# STM32_BalanceCar.net
KiCad netlist of a schematic drawn in Altium Designer
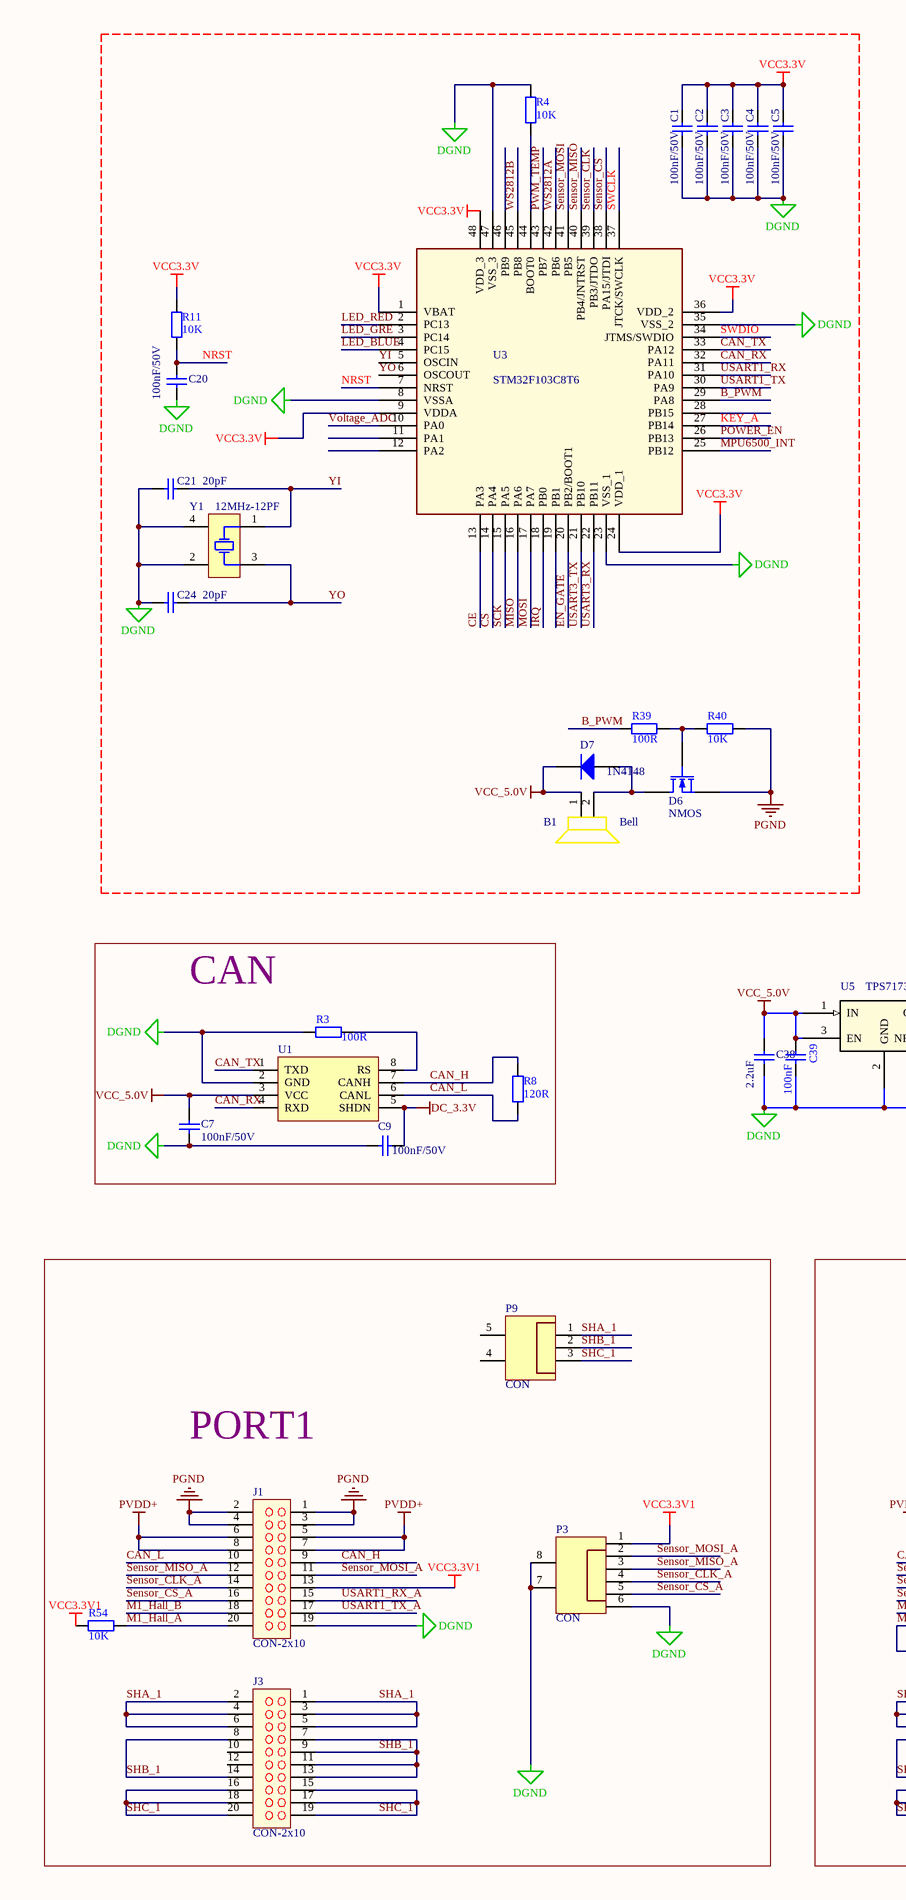
[diagram p0: STM32_BalanceCar.SchDoc, left]
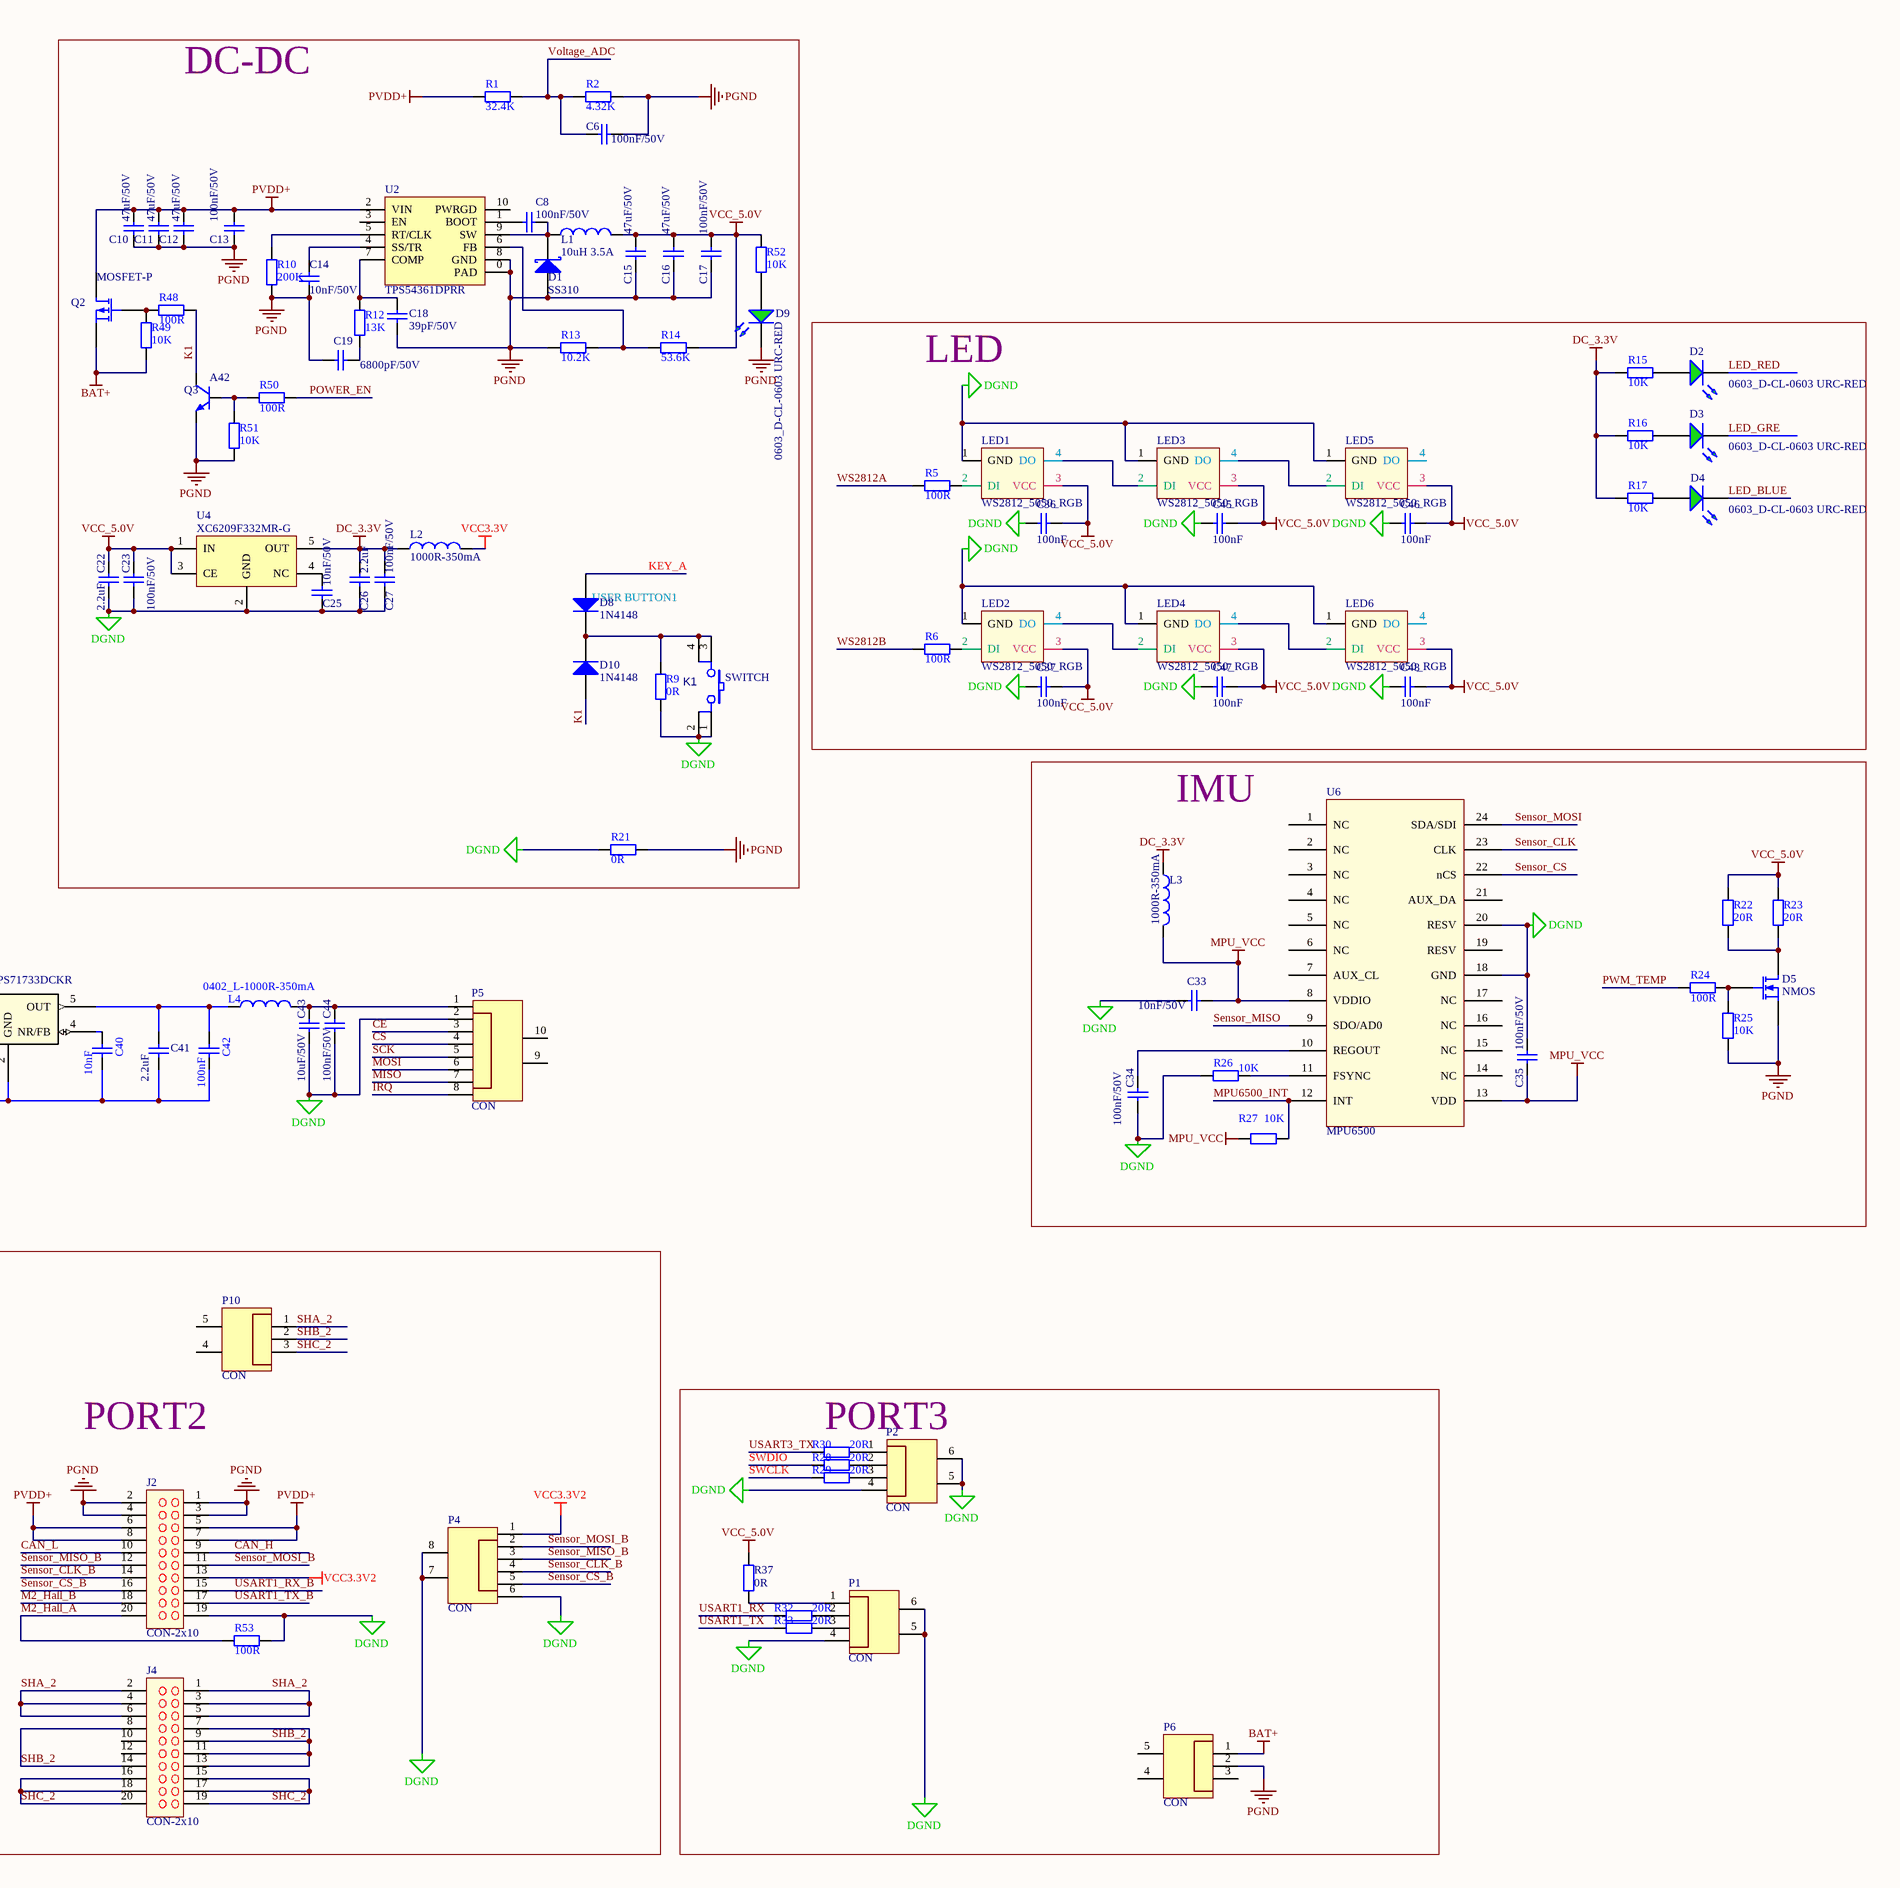
[diagram p1: STM32_BalanceCar.SchDoc, right]

(export (version "E")
  (design (tool "Eeschema 10.0.6"))
  (components
    (comp (ref "B1") (value "Bell") (footprint "Bell") (libsource (lib "Bell") (part "Bell")))
    (comp (ref "C1")
      (value "100nF/50V")
      (footprint "0402_C")
      (description "Capacitor")
      (fields (field (name "PUBLISHER") "Altium Limited"))
      (libsource (lib "") (part "Cap_1"))
    )
    (comp (ref "C2")
      (value "100nF/50V")
      (footprint "0402_C")
      (description "Capacitor")
      (fields (field (name "PUBLISHER") "Altium Limited"))
      (libsource (lib "") (part "Cap_1"))
    )
    (comp (ref "C3")
      (value "100nF/50V")
      (footprint "0402_C")
      (description "Capacitor")
      (fields (field (name "PUBLISHER") "Altium Limited"))
      (libsource (lib "") (part "Cap_1"))
    )
    (comp (ref "C4")
      (value "100nF/50V")
      (footprint "0402_C")
      (description "Capacitor")
      (fields (field (name "PUBLISHER") "Altium Limited"))
      (libsource (lib "") (part "Cap_1"))
    )
    (comp (ref "C5")
      (value "100nF/50V")
      (footprint "0402_C")
      (description "Capacitor")
      (fields (field (name "PUBLISHER") "Altium Limited"))
      (libsource (lib "") (part "Cap_1"))
    )
    (comp (ref "C6")
      (value "100nF/50V")
      (footprint "0402_C")
      (description "Capacitor")
      (fields (field (name "PUBLISHER") "Altium Limited"))
      (libsource (lib "") (part "Cap_1"))
    )
    (comp (ref "C7")
      (value "100nF/50V")
      (footprint "0402_C")
      (description "Capacitor")
      (fields (field (name "PUBLISHER") "Altium Limited"))
      (libsource (lib "Miscellaneous Devices") (part "Cap"))
    )
    (comp (ref "C8")
      (value "100nF/50V")
      (footprint "0402_C")
      (description "Capacitor")
      (fields (field (name "PUBLISHER") "Altium Limited"))
      (libsource (lib "") (part "Cap_1"))
    )
    (comp (ref "C9")
      (value "100nF/50V")
      (footprint "0402_C")
      (description "Capacitor")
      (fields (field (name "PUBLISHER") "Altium Limited"))
      (libsource (lib "") (part "Cap_1"))
    )
    (comp (ref "C10")
      (value "47uF/50V")
      (footprint "1210_C")
      (description "Capacitor")
      (fields (field (name "PUBLISHER") "Altium Limited"))
      (libsource (lib "Miscellaneous Devices") (part "Cap"))
    )
    (comp (ref "C11")
      (value "47uF/50V")
      (footprint "1210_C")
      (description "Capacitor")
      (fields (field (name "PUBLISHER") "Altium Limited"))
      (libsource (lib "Miscellaneous Devices") (part "Cap"))
    )
    (comp (ref "C12")
      (value "47uF/50V")
      (footprint "1210_C")
      (description "Capacitor")
      (fields (field (name "PUBLISHER") "Altium Limited"))
      (libsource (lib "Miscellaneous Devices") (part "Cap"))
    )
    (comp (ref "C13")
      (value "100nF/50V")
      (footprint "0402_C")
      (description "Capacitor")
      (fields (field (name "PUBLISHER") "Altium Limited"))
      (libsource (lib "") (part "Cap_1"))
    )
    (comp (ref "C14")
      (value "10nF/50V")
      (footprint "0402_C")
      (description "Capacitor")
      (fields (field (name "PUBLISHER") "Altium Limited"))
      (libsource (lib "Miscellaneous Devices") (part "Cap"))
    )
    (comp (ref "C15")
      (value "47uF/50V")
      (footprint "1206_C")
      (description "Capacitor")
      (fields (field (name "PUBLISHER") "Altium Limited"))
      (libsource (lib "Miscellaneous Devices") (part "Cap"))
    )
    (comp (ref "C16")
      (value "47uF/50V")
      (footprint "1206_C")
      (description "Capacitor")
      (fields (field (name "PUBLISHER") "Altium Limited"))
      (libsource (lib "Miscellaneous Devices") (part "Cap"))
    )
    (comp (ref "C17")
      (value "100nF/50V")
      (footprint "0402_C")
      (description "Capacitor")
      (fields (field (name "PUBLISHER") "Altium Limited"))
      (libsource (lib "") (part "Cap_1"))
    )
    (comp (ref "C18")
      (value "39pF/50V")
      (footprint "0402_C")
      (description "Capacitor")
      (fields (field (name "PUBLISHER") "Altium Limited"))
      (libsource (lib "Miscellaneous Devices") (part "Cap"))
    )
    (comp (ref "C19")
      (value "6800pF/50V")
      (footprint "0402_C")
      (description "Capacitor")
      (fields (field (name "PUBLISHER") "Altium Limited"))
      (libsource (lib "") (part "Cap_1"))
    )
    (comp (ref "C20")
      (value "100nF/50V")
      (footprint "0402_C")
      (description "Capacitor")
      (fields (field (name "PUBLISHER") "Altium Limited"))
      (libsource (lib "") (part "Cap_1"))
    )
    (comp (ref "C21")
      (value "20pF")
      (footprint "0402_C")
      (description "Capacitor")
      (fields (field (name "PUBLISHER") "Altium Limited"))
      (libsource (lib "") (part "Cap_1"))
    )
    (comp (ref "C22")
      (value "2.2uF")
      (footprint "0402_C")
      (description "Capacitor")
      (fields (field (name "PUBLISHER") "Altium Limited"))
      (libsource (lib "") (part "Cap_1"))
    )
    (comp (ref "C23")
      (value "100nF/50V")
      (footprint "0402_C")
      (description "Capacitor")
      (fields (field (name "PUBLISHER") "Altium Limited"))
      (libsource (lib "") (part "Cap_1"))
    )
    (comp (ref "C24")
      (value "20pF")
      (footprint "0402_C")
      (description "Capacitor")
      (fields (field (name "PUBLISHER") "Altium Limited"))
      (libsource (lib "") (part "Cap_1"))
    )
    (comp (ref "C25")
      (value "10nF/50V")
      (footprint "0402_C")
      (description "Capacitor")
      (fields (field (name "PUBLISHER") "Altium Limited"))
      (libsource (lib "") (part "Cap_1"))
    )
    (comp (ref "C26")
      (value "2.2uF")
      (footprint "0402_C")
      (description "Capacitor")
      (fields (field (name "PUBLISHER") "Altium Limited"))
      (libsource (lib "") (part "Cap_1"))
    )
    (comp (ref "C27")
      (value "100nF/50V")
      (footprint "0402_C")
      (description "Capacitor")
      (fields (field (name "PUBLISHER") "Altium Limited"))
      (libsource (lib "") (part "Cap_1"))
    )
    (comp (ref "C33")
      (value "10nF/50V")
      (footprint "0402_C")
      (description "Capacitor")
      (fields (field (name "PUBLISHER") "Altium Limited"))
      (libsource (lib "Miscellaneous Devices") (part "Cap"))
    )
    (comp (ref "C34")
      (value "100nF/50V")
      (footprint "0402_C")
      (description "Capacitor")
      (fields (field (name "PUBLISHER") "Altium Limited"))
      (libsource (lib "") (part "Cap_1"))
    )
    (comp (ref "C35")
      (value "100nF/50V")
      (footprint "0402_C")
      (description "Capacitor")
      (fields (field (name "PUBLISHER") "Altium Limited"))
      (libsource (lib "") (part "Cap_1"))
    )
    (comp (ref "C36")
      (value "100nF")
      (footprint "0402_C")
      (description "Capacitor")
      (fields (field (name "PUBLISHER") "Altium Limited"))
      (libsource (lib "Cap") (part "Cap"))
    )
    (comp (ref "C37")
      (value "100nF")
      (footprint "0402_C")
      (description "Capacitor")
      (fields (field (name "PUBLISHER") "Altium Limited"))
      (libsource (lib "Cap") (part "Cap"))
    )
    (comp (ref "C38")
      (value "2.2uF")
      (footprint "0603_C")
      (description "Capacitor")
      (fields (field (name "PUBLISHER") "Altium Limited"))
      (libsource (lib "") (part "Cap_1"))
    )
    (comp (ref "C39")
      (value "100nF")
      (footprint "0402_C")
      (description "Capacitor")
      (fields (field (name "PUBLISHER") "Altium Limited"))
      (libsource (lib "") (part "Cap_1"))
    )
    (comp (ref "C40")
      (value "10nF")
      (footprint "0402_C")
      (description "Capacitor")
      (fields (field (name "PUBLISHER") "Altium Limited"))
      (libsource (lib "") (part "Cap_1"))
    )
    (comp (ref "C41")
      (value "2.2uF")
      (footprint "0603_C")
      (description "Capacitor")
      (fields (field (name "PUBLISHER") "Altium Limited"))
      (libsource (lib "") (part "Cap_1"))
    )
    (comp (ref "C42")
      (value "100nF")
      (footprint "0402_C")
      (description "Capacitor")
      (fields (field (name "PUBLISHER") "Altium Limited"))
      (libsource (lib "") (part "Cap_1"))
    )
    (comp (ref "C43")
      (value "10uF/50V")
      (footprint "0603_C")
      (description "Capacitor")
      (fields (field (name "PUBLISHER") "Altium Limited"))
      (libsource (lib "") (part "Cap_1"))
    )
    (comp (ref "C44")
      (value "100nF/50V")
      (footprint "0603_C")
      (description "Capacitor")
      (fields (field (name "PUBLISHER") "Altium Limited"))
      (libsource (lib "") (part "Cap_1"))
    )
    (comp (ref "C45")
      (value "100nF")
      (footprint "0402_C")
      (description "Capacitor")
      (fields (field (name "PUBLISHER") "Altium Limited"))
      (libsource (lib "Cap") (part "Cap"))
    )
    (comp (ref "C46")
      (value "100nF")
      (footprint "0402_C")
      (description "Capacitor")
      (fields (field (name "PUBLISHER") "Altium Limited"))
      (libsource (lib "Cap") (part "Cap"))
    )
    (comp (ref "C47")
      (value "100nF")
      (footprint "0402_C")
      (description "Capacitor")
      (fields (field (name "PUBLISHER") "Altium Limited"))
      (libsource (lib "Cap") (part "Cap"))
    )
    (comp (ref "C48")
      (value "100nF")
      (footprint "0402_C")
      (description "Capacitor")
      (fields (field (name "PUBLISHER") "Altium Limited"))
      (libsource (lib "Cap") (part "Cap"))
    )
    (comp (ref "D1")
      (value "SS310")
      (footprint "DO-214-AC(SMA)")
      (description "Diode Schottky")
      (fields (field (name "PUBLISHER") "Altium Limited"))
      (libsource (lib "Diode Schottky") (part "Diode Schottky"))
    )
    (comp (ref "D2")
      (value "0603_D-CL-0603 URC-RED")
      (footprint "0603_D")
      (description "LED")
      (libsource (lib "LED") (part "LED"))
    )
    (comp (ref "D3")
      (value "0603_D-CL-0603 URC-RED")
      (footprint "0603_D")
      (description "LED")
      (libsource (lib "LED") (part "LED"))
    )
    (comp (ref "D4")
      (value "0603_D-CL-0603 URC-RED")
      (footprint "0603_D")
      (description "LED")
      (libsource (lib "LED") (part "LED"))
    )
    (comp (ref "D5")
      (value "NMOS")
      (footprint "SOT23-3")
      (fields (field (name "PUBLISHER") "Altium Limited"))
      (libsource (lib "MOSFET-N") (part "MOSFET"))
    )
    (comp (ref "D6")
      (value "NMOS")
      (footprint "SOT23-3")
      (fields (field (name "PUBLISHER") "Altium Limited"))
      (libsource (lib "") (part "MOSFET_1"))
    )
    (comp (ref "D7")
      (value "1N4148")
      (footprint "SOD-123")
      (description "Diode")
      (fields (field (name "PUBLISHER") "Altium Limited"))
      (libsource (lib "1N4148") (part "1N4148"))
    )
    (comp (ref "D8")
      (value "1N4148")
      (footprint "SOD-123")
      (description "Diode")
      (fields (field (name "PUBLISHER") "Altium Limited"))
      (libsource (lib "1N4148") (part "1N4148"))
    )
    (comp (ref "D9")
      (value "0603_D-CL-0603 URC-RED")
      (footprint "0603_D")
      (description "LED")
      (libsource (lib "") (part "LED_1"))
    )
    (comp (ref "D10")
      (value "1N4148")
      (footprint "SOD-123")
      (description "Diode")
      (fields (field (name "PUBLISHER") "Altium Limited"))
      (libsource (lib "1N4148") (part "1N4148"))
    )
    (comp (ref "J1") (value "CON-2x10") (footprint "CON-2x10") (libsource (lib "CON-2x10") (part "CON-2x10")))
    (comp (ref "J2") (value "CON-2x10") (footprint "CON-2x10") (libsource (lib "CON-2x10") (part "CON-2x10")))
    (comp (ref "J3") (value "CON-2x10") (footprint "CON-2x10") (libsource (lib "CON-2x10") (part "CON-2x10")))
    (comp (ref "J4") (value "CON-2x10") (footprint "CON-2x10") (libsource (lib "CON-2x10") (part "CON-2x10")))
    (comp (ref "K1")
      (value "SWITCH")
      (footprint "SW_3x4x2.5")
      (description "Non-Open Push-Button 0.1A 24V")
      (fields
        (field (name "INTERNAL_PART_NUMBER") "MCD-00002")
        (field (name "MANUFACTURER_PART_NUMBER") "TD-0341")
        (field (name "PROVIDED_BY") "SUBCO")
      )
      (libsource (lib "MCD_PARTS_database") (part "SW-PUSH-CMS"))
    )
    (comp (ref "L1")
      (value "10uH 3.5A")
      (footprint "TMPC0603H")
      (description "Inductor")
      (fields (field (name "PUBLISHER") "Altium Limited"))
      (libsource (lib "Miscellaneous Devices") (part "Inductor"))
    )
    (comp (ref "L2")
      (value "1000R-350mA")
      (footprint "0402_L")
      (description "Inductor")
      (fields (field (name "PUBLISHER") "Altium Limited"))
      (libsource (lib "Miscellaneous Devices") (part "Inductor"))
    )
    (comp (ref "L3")
      (value "1000R-350mA")
      (footprint "0402_L")
      (description "Inductor")
      (fields (field (name "PUBLISHER") "Altium Limited"))
      (libsource (lib "Miscellaneous Devices") (part "Inductor"))
    )
    (comp (ref "L4")
      (value "0402_L-1000R-350mA")
      (footprint "0402_L")
      (description "Inductor")
      (fields (field (name "PUBLISHER") "Altium Limited"))
      (libsource (lib "Miscellaneous Devices") (part "Inductor"))
    )
    (comp (ref "LED1")
      (value "WS2812_5050_RGB")
      (footprint "RGB_50X50")
      (libsource (lib "WS2812_5050_RGB") (part "WS2812_5050_RGB"))
    )
    (comp (ref "LED2")
      (value "WS2812_5050_RGB")
      (footprint "RGB_50X50")
      (libsource (lib "WS2812_5050_RGB") (part "WS2812_5050_RGB"))
    )
    (comp (ref "LED3")
      (value "WS2812_5050_RGB")
      (footprint "RGB_50X50")
      (libsource (lib "WS2812_5050_RGB") (part "WS2812_5050_RGB"))
    )
    (comp (ref "LED4")
      (value "WS2812_5050_RGB")
      (footprint "RGB_50X50")
      (libsource (lib "WS2812_5050_RGB") (part "WS2812_5050_RGB"))
    )
    (comp (ref "LED5")
      (value "WS2812_5050_RGB")
      (footprint "RGB_50X50")
      (libsource (lib "WS2812_5050_RGB") (part "WS2812_5050_RGB"))
    )
    (comp (ref "LED6")
      (value "WS2812_5050_RGB")
      (footprint "RGB_50X50")
      (libsource (lib "WS2812_5050_RGB") (part "WS2812_5050_RGB"))
    )
    (comp (ref "P1") (value "CON") (footprint "BM04B-GHS-TBT(TOP)") (libsource (lib "CON-4") (part "CON-4")))
    (comp (ref "P2") (value "CON") (footprint "BM04B-GHS-TBT(TOP)") (libsource (lib "CON-4") (part "CON-4")))
    (comp (ref "P3") (value "CON") (footprint "BM06B-GHS-TBT(TOP)") (libsource (lib "CON-6") (part "CON-6")))
    (comp (ref "P4") (value "CON") (footprint "BM06B-GHS-TBT(TOP)") (libsource (lib "CON-6") (part "CON-6")))
    (comp (ref "P5") (value "CON") (footprint "NRF24L01_L") (libsource (lib "CON-8") (part "CON-8")))
    (comp (ref "P6") (value "CON") (footprint "XT30U-F") (libsource (lib "CON-3") (part "CON-3")))
    (comp (ref "P9") (value "CON") (footprint "MR30PW-FB") (libsource (lib "CON-3") (part "CON-3")))
    (comp (ref "P10") (value "CON") (footprint "MR30PW-FB") (libsource (lib "CON-3") (part "CON-3")))
    (comp (ref "Q2")
      (value "MOSFET-P")
      (footprint "DFN5X6")
      (description "P-Channel MOSFET")
      (libsource (lib "MOSFET-P") (part "MOSFET-P"))
    )
    (comp (ref "Q3") (value "A42") (footprint "SOT23-3") (libsource (lib "A42") (part "A42")))
    (comp (ref "R1")
      (value "32.4K")
      (footprint "0402_R")
      (description "Resistor")
      (fields (field (name "PUBLISHER") "Altium Limited"))
      (libsource (lib "") (part "Res2_3"))
    )
    (comp (ref "R2")
      (value "4.32K")
      (footprint "0402_R")
      (description "Resistor")
      (fields (field (name "PUBLISHER") "Altium Limited"))
      (libsource (lib "") (part "Res2_3"))
    )
    (comp (ref "R3")
      (value "100R")
      (footprint "0402_R")
      (description "Resistor")
      (fields (field (name "PUBLISHER") "Altium Limited"))
      (libsource (lib "Miscellaneous Devices") (part "Res2"))
    )
    (comp (ref "R4")
      (value "10K")
      (footprint "0402_R")
      (description "Resistor")
      (fields (field (name "PUBLISHER") "Altium Limited"))
      (libsource (lib "") (part "Res2_1"))
    )
    (comp (ref "R5")
      (value "100R")
      (footprint "0402_R")
      (description "Resistor")
      (fields (field (name "PUBLISHER") "Altium Limited"))
      (libsource (lib "") (part "Res2_3"))
    )
    (comp (ref "R6")
      (value "100R")
      (footprint "0402_R")
      (description "Resistor")
      (fields (field (name "PUBLISHER") "Altium Limited"))
      (libsource (lib "Miscellaneous Devices") (part "Res2"))
    )
    (comp (ref "R8")
      (value "120R")
      (footprint "0603_R")
      (description "Resistor")
      (fields (field (name "PUBLISHER") "Altium Limited"))
      (libsource (lib "") (part "Res2_1"))
    )
    (comp (ref "R9")
      (value "0R")
      (footprint "0402_R")
      (description "Resistor")
      (fields (field (name "PUBLISHER") "Altium Limited"))
      (libsource (lib "") (part "Res2_1"))
    )
    (comp (ref "R10")
      (value "200K")
      (footprint "0402_R")
      (description "Resistor")
      (fields (field (name "PUBLISHER") "Altium Limited"))
      (libsource (lib "") (part "Res2_1"))
    )
    (comp (ref "R11")
      (value "10K")
      (footprint "0402_R")
      (description "Resistor")
      (fields (field (name "PUBLISHER") "Altium Limited"))
      (libsource (lib "") (part "Res2_1"))
    )
    (comp (ref "R12")
      (value "13K")
      (footprint "0402_R")
      (description "Resistor")
      (fields (field (name "PUBLISHER") "Altium Limited"))
      (libsource (lib "") (part "Res2_1"))
    )
    (comp (ref "R13")
      (value "10.2K")
      (footprint "0402_R")
      (description "Resistor")
      (fields (field (name "PUBLISHER") "Altium Limited"))
      (libsource (lib "") (part "Res2_3"))
    )
    (comp (ref "R14")
      (value "53.6K")
      (footprint "0402_R")
      (description "Resistor")
      (fields (field (name "PUBLISHER") "Altium Limited"))
      (libsource (lib "") (part "Res2_3"))
    )
    (comp (ref "R15")
      (value "10K")
      (footprint "0402_R")
      (description "Resistor")
      (fields (field (name "PUBLISHER") "Altium Limited"))
      (libsource (lib "Miscellaneous Devices") (part "Res2"))
    )
    (comp (ref "R16")
      (value "10K")
      (footprint "0402_R")
      (description "Resistor")
      (fields (field (name "PUBLISHER") "Altium Limited"))
      (libsource (lib "Miscellaneous Devices") (part "Res2"))
    )
    (comp (ref "R17")
      (value "10K")
      (footprint "0402_R")
      (description "Resistor")
      (fields (field (name "PUBLISHER") "Altium Limited"))
      (libsource (lib "Miscellaneous Devices") (part "Res2"))
    )
    (comp (ref "R21")
      (value "0R")
      (footprint "0805_R")
      (description "Resistor")
      (fields (field (name "PUBLISHER") "Altium Limited"))
      (libsource (lib "") (part "Res2_3"))
    )
    (comp (ref "R22")
      (value "20R")
      (footprint "0805_R")
      (description "Resistor")
      (fields (field (name "PUBLISHER") "Altium Limited"))
      (libsource (lib "") (part "Res2_2"))
    )
    (comp (ref "R23")
      (value "20R")
      (footprint "0805_R")
      (description "Resistor")
      (fields (field (name "PUBLISHER") "Altium Limited"))
      (libsource (lib "") (part "Res2_2"))
    )
    (comp (ref "R24")
      (value "100R")
      (footprint "0402_R")
      (description "Resistor")
      (fields (field (name "PUBLISHER") "Altium Limited"))
      (libsource (lib "Miscellaneous Devices") (part "Res2"))
    )
    (comp (ref "R25")
      (value "10K")
      (footprint "0402_R")
      (description "Resistor")
      (fields (field (name "PUBLISHER") "Altium Limited"))
      (libsource (lib "") (part "Res2_2"))
    )
    (comp (ref "R26")
      (value "10K")
      (footprint "0402_R")
      (description "Resistor")
      (fields (field (name "PUBLISHER") "Altium Limited"))
      (libsource (lib "") (part "Res2_3"))
    )
    (comp (ref "R27")
      (value "10K")
      (footprint "0402_R")
      (description "Resistor")
      (fields (field (name "PUBLISHER") "Altium Limited"))
      (libsource (lib "") (part "Res2_3"))
    )
    (comp (ref "R28")
      (value "20R")
      (footprint "0402_R")
      (description "Resistor")
      (fields (field (name "PUBLISHER") "Altium Limited"))
      (libsource (lib "") (part "Res2_3"))
    )
    (comp (ref "R29")
      (value "20R")
      (footprint "0402_R")
      (description "Resistor")
      (fields (field (name "PUBLISHER") "Altium Limited"))
      (libsource (lib "") (part "Res2_3"))
    )
    (comp (ref "R30")
      (value "20R")
      (footprint "0402_R")
      (description "Resistor")
      (fields (field (name "PUBLISHER") "Altium Limited"))
      (libsource (lib "Miscellaneous Devices") (part "Res2"))
    )
    (comp (ref "R32")
      (value "20R")
      (footprint "0402_R")
      (description "Resistor")
      (fields (field (name "PUBLISHER") "Altium Limited"))
      (libsource (lib "") (part "Res2_3"))
    )
    (comp (ref "R33")
      (value "20R")
      (footprint "0402_R")
      (description "Resistor")
      (fields (field (name "PUBLISHER") "Altium Limited"))
      (libsource (lib "") (part "Res2_3"))
    )
    (comp (ref "R37")
      (value "0R")
      (footprint "0603_R")
      (description "Resistor")
      (libsource (lib "Res") (part "Res"))
    )
    (comp (ref "R39")
      (value "100R")
      (footprint "0402_R")
      (description "Resistor")
      (fields (field (name "PUBLISHER") "Altium Limited"))
      (libsource (lib "Miscellaneous Devices") (part "Res2"))
    )
    (comp (ref "R40")
      (value "10K")
      (footprint "0402_R")
      (description "Resistor")
      (fields (field (name "PUBLISHER") "Altium Limited"))
      (libsource (lib "") (part "Res2_3"))
    )
    (comp (ref "R48")
      (value "100R")
      (footprint "0402_R")
      (description "Resistor")
      (fields (field (name "PUBLISHER") "Altium Limited"))
      (libsource (lib "Miscellaneous Devices") (part "Res2"))
    )
    (comp (ref "R49")
      (value "10K")
      (footprint "0402_R")
      (description "Resistor")
      (fields (field (name "PUBLISHER") "Altium Limited"))
      (libsource (lib "") (part "Res2_1"))
    )
    (comp (ref "R50")
      (value "100R")
      (footprint "0402_R")
      (description "Resistor")
      (fields (field (name "PUBLISHER") "Altium Limited"))
      (libsource (lib "Miscellaneous Devices") (part "Res2"))
    )
    (comp (ref "R51")
      (value "10K")
      (footprint "0402_R")
      (description "Resistor")
      (fields (field (name "PUBLISHER") "Altium Limited"))
      (libsource (lib "") (part "Res2_1"))
    )
    (comp (ref "R52")
      (value "10K")
      (footprint "0402_R")
      (description "Resistor")
      (fields (field (name "PUBLISHER") "Altium Limited"))
      (libsource (lib "") (part "Res2_1"))
    )
    (comp (ref "R53")
      (value "100R")
      (footprint "0402_R")
      (description "Resistor")
      (fields (field (name "PUBLISHER") "Altium Limited"))
      (libsource (lib "Miscellaneous Devices") (part "Res2"))
    )
    (comp (ref "R54")
      (value "10K")
      (footprint "0402_R")
      (description "Resistor")
      (fields (field (name "PUBLISHER") "Altium Limited"))
      (libsource (lib "") (part "Res2_3"))
    )
    (comp (ref "U1") (value "1042") (footprint "SOP-8") (libsource (lib "MAX3051") (part "MAX3051")))
    (comp (ref "U2")
      (value "TPS54361DPRR")
      (footprint "TPS54361")
      (libsource (lib "TPS54361") (part "TPS54361"))
    )
    (comp (ref "U3")
      (value "STM32F103C8T6")
      (footprint "LQFP-48")
      (libsource (lib "STM32F103CBT6") (part "STM32F103CBT6"))
    )
    (comp (ref "U4")
      (value "XC6209F332MR-G")
      (footprint "SOT23-5")
      (libsource (lib "XC6228D332VR-G") (part "XC6228D332VR-G"))
    )
    (comp (ref "U5")
      (value "TPS71733DCKR")
      (footprint "SOT23-5")
      (description "Imported")
      (fields
        (field (name "MANUFACTURER_PART_NUMBER") "tps71701_dck_5")
        (field (name "GENERIC_PART_NUMBER") "TPS71701")
      )
      (libsource (lib "AG_FC_V3_4_00_LD_20191122") (part "TPS71733DCKR"))
    )
    (comp (ref "U6") (value "MPU6500") (footprint "MPU6500") (libsource (lib "MPU6500") (part "MPU6500")))
    (comp (ref "Y1")
      (value "12MHz-12PF")
      (footprint "XTAL_SMD_3.2X2.5_4P")
      (description "XTAL-4P")
      (libsource (lib "XTAL_4P") (part "XTAL-4P"))
    )
  )
  (nets
    (net (code "1") (name "/B_PWM") (class "Default")
      (node (ref "R39") (pin "2") (pinfunction "2_2") (pintype "passive"))
      (node (ref "U3") (pin "29") (pinfunction "PA8_29") (pintype "passive"))
    )
    (net (code "2") (name "/CAN_H") (class "Default")
      (node (ref "J1") (pin "9") (pintype "passive"))
      (node (ref "J2") (pin "9") (pintype "passive"))
      (node (ref "R8") (pin "1") (pinfunction "1_1") (pintype "passive"))
      (node (ref "U1") (pin "7") (pinfunction "CANH_7") (pintype "passive"))
    )
    (net (code "3") (name "/CAN_L") (class "Default")
      (node (ref "J1") (pin "10") (pintype "passive"))
      (node (ref "J2") (pin "10") (pintype "passive"))
      (node (ref "R8") (pin "2") (pinfunction "2_2") (pintype "passive"))
      (node (ref "U1") (pin "6") (pinfunction "CANL_6") (pintype "passive"))
    )
    (net (code "4") (name "/CAN_RX") (class "Default")
      (node (ref "U1") (pin "4") (pinfunction "RXD_4") (pintype "passive"))
      (node (ref "U3") (pin "32") (pinfunction "PA11_32") (pintype "passive"))
    )
    (net (code "5") (name "/CAN_TX") (class "Default")
      (node (ref "U1") (pin "1") (pinfunction "TXD_1") (pintype "passive"))
      (node (ref "U3") (pin "33") (pinfunction "PA12_33") (pintype "passive"))
    )
    (net (code "6") (name "/CE") (class "Default")
      (node (ref "P5") (pin "3") (pintype "passive"))
      (node (ref "U3") (pin "13") (pinfunction "PA3_13") (pintype "passive"))
    )
    (net (code "7") (name "/CS") (class "Default")
      (node (ref "P5") (pin "4") (pintype "passive"))
      (node (ref "U3") (pin "14") (pinfunction "PA4_14") (pintype "passive"))
    )
    (net (code "8") (name "/EN_GATE") (class "Default")
      (node (ref "U3") (pin "20") (pinfunction "PB2/BOOT1_20") (pintype "passive"))
    )
    (net (code "9") (name "/IRQ") (class "Default")
      (node (ref "P5") (pin "8") (pintype "passive"))
      (node (ref "U3") (pin "18") (pinfunction "PB0_18") (pintype "passive"))
    )
    (net (code "10") (name "/K1") (class "Default")
      (node (ref "D10") (pin "1") (pinfunction "A_1") (pintype "passive"))
      (node (ref "Q3") (pin "3") (pinfunction "C_3") (pintype "passive"))
      (node (ref "R48") (pin "1") (pinfunction "1_1") (pintype "passive"))
    )
    (net (code "11") (name "/KEY_A") (class "Default")
      (node (ref "D8") (pin "1") (pinfunction "A_1") (pintype "passive"))
      (node (ref "U3") (pin "27") (pinfunction "PB14_27") (pintype "passive"))
    )
    (net (code "12") (name "/LED_BLUE") (class "Default")
      (node (ref "D4") (pin "2") (pinfunction "K_2") (pintype "passive"))
      (node (ref "U3") (pin "4") (pinfunction "PC15_4") (pintype "passive"))
    )
    (net (code "13") (name "/LED_GRE") (class "Default")
      (node (ref "D3") (pin "2") (pinfunction "K_2") (pintype "passive"))
      (node (ref "U3") (pin "3") (pinfunction "PC14_3") (pintype "passive"))
    )
    (net (code "14") (name "/LED_RED") (class "Default")
      (node (ref "D2") (pin "2") (pinfunction "K_2") (pintype "passive"))
      (node (ref "U3") (pin "2") (pinfunction "PC13_2") (pintype "passive"))
    )
    (net (code "15") (name "/M1_Hall_A") (class "Default")
      (node (ref "J1") (pin "20") (pintype "passive"))
      (node (ref "R54") (pin "2") (pinfunction "2_2") (pintype "passive"))
    )
    (net (code "16") (name "/M1_Hall_B") (class "Default") (node (ref "J1") (pin "18") (pintype "passive")))
    (net (code "17") (name "/M2_Hall_A") (class "Default")
      (node (ref "J2") (pin "20") (pintype "passive"))
      (node (ref "R53") (pin "2") (pinfunction "2_2") (pintype "passive"))
    )
    (net (code "18") (name "/M2_Hall_B") (class "Default") (node (ref "J2") (pin "18") (pintype "passive")))
    (net (code "19") (name "/MISO") (class "Default")
      (node (ref "P5") (pin "7") (pintype "passive"))
      (node (ref "U3") (pin "16") (pinfunction "PA6_16") (pintype "passive"))
    )
    (net (code "20") (name "/MOSI") (class "Default")
      (node (ref "P5") (pin "6") (pintype "passive"))
      (node (ref "U3") (pin "17") (pinfunction "PA7_17") (pintype "passive"))
    )
    (net (code "21") (name "/MPU6500_INT") (class "Default")
      (node (ref "R27") (pin "2") (pinfunction "2_2") (pintype "passive"))
      (node (ref "U3") (pin "25") (pinfunction "PB12_25") (pintype "passive"))
      (node (ref "U6") (pin "12") (pinfunction "INT_12") (pintype "passive"))
    )
    (net (code "22") (name "/NRST") (class "Default")
      (node (ref "C20") (pin "1") (pinfunction "1_1") (pintype "passive"))
      (node (ref "R11") (pin "2") (pinfunction "2_2") (pintype "passive"))
      (node (ref "U3") (pin "7") (pinfunction "NRST_7") (pintype "passive"))
    )
    (net (code "23") (name "/POWER_EN") (class "Default")
      (node (ref "R50") (pin "1") (pinfunction "1_1") (pintype "passive"))
      (node (ref "U3") (pin "26") (pinfunction "PB13_26") (pintype "passive"))
    )
    (net (code "24") (name "/PWM_TEMP") (class "Default")
      (node (ref "R24") (pin "2") (pinfunction "2_2") (pintype "passive"))
      (node (ref "U3") (pin "43") (pinfunction "PB7_43") (pintype "passive"))
    )
    (net (code "25") (name "/SCK") (class "Default")
      (node (ref "P5") (pin "5") (pintype "passive"))
      (node (ref "U3") (pin "15") (pinfunction "PA5_15") (pintype "passive"))
    )
    (net (code "26") (name "/SHA_1") (class "Default")
      (node (ref "J3") (pin "1") (pintype "passive"))
      (node (ref "J3") (pin "2") (pintype "passive"))
      (node (ref "J3") (pin "3") (pintype "passive"))
      (node (ref "J3") (pin "4") (pintype "passive"))
      (node (ref "J3") (pin "5") (pintype "passive"))
      (node (ref "J3") (pin "6") (pintype "passive"))
      (node (ref "P9") (pin "1") (pintype "passive"))
    )
    (net (code "27") (name "/SHA_2") (class "Default")
      (node (ref "J4") (pin "1") (pintype "passive"))
      (node (ref "J4") (pin "2") (pintype "passive"))
      (node (ref "J4") (pin "3") (pintype "passive"))
      (node (ref "J4") (pin "4") (pintype "passive"))
      (node (ref "J4") (pin "5") (pintype "passive"))
      (node (ref "J4") (pin "6") (pintype "passive"))
      (node (ref "P10") (pin "1") (pintype "passive"))
    )
    (net (code "28") (name "/SHB_1") (class "Default")
      (node (ref "J3") (pin "11") (pintype "passive"))
      (node (ref "J3") (pin "13") (pintype "passive"))
      (node (ref "J3") (pin "14") (pintype "passive"))
      (node (ref "J3") (pin "7") (pintype "passive"))
      (node (ref "J3") (pin "8") (pintype "passive"))
      (node (ref "J3") (pin "9") (pintype "passive"))
      (node (ref "P9") (pin "2") (pintype "passive"))
    )
    (net (code "29") (name "/SHB_2") (class "Default")
      (node (ref "J4") (pin "11") (pintype "passive"))
      (node (ref "J4") (pin "13") (pintype "passive"))
      (node (ref "J4") (pin "14") (pintype "passive"))
      (node (ref "J4") (pin "7") (pintype "passive"))
      (node (ref "J4") (pin "8") (pintype "passive"))
      (node (ref "J4") (pin "9") (pintype "passive"))
      (node (ref "P10") (pin "2") (pintype "passive"))
    )
    (net (code "30") (name "/SHC_1") (class "Default")
      (node (ref "J3") (pin "15") (pintype "passive"))
      (node (ref "J3") (pin "16") (pintype "passive"))
      (node (ref "J3") (pin "17") (pintype "passive"))
      (node (ref "J3") (pin "18") (pintype "passive"))
      (node (ref "J3") (pin "19") (pintype "passive"))
      (node (ref "J3") (pin "20") (pintype "passive"))
      (node (ref "P9") (pin "3") (pintype "passive"))
    )
    (net (code "31") (name "/SHC_2") (class "Default")
      (node (ref "J4") (pin "15") (pintype "passive"))
      (node (ref "J4") (pin "16") (pintype "passive"))
      (node (ref "J4") (pin "17") (pintype "passive"))
      (node (ref "J4") (pin "18") (pintype "passive"))
      (node (ref "J4") (pin "19") (pintype "passive"))
      (node (ref "J4") (pin "20") (pintype "passive"))
      (node (ref "P10") (pin "3") (pintype "passive"))
    )
    (net (code "32") (name "/SWCLK") (class "Default")
      (node (ref "R29") (pin "1") (pinfunction "1_1") (pintype "passive"))
      (node (ref "U3") (pin "37") (pinfunction "JTCK/SWCLK_37") (pintype "passive"))
    )
    (net (code "33") (name "/SWDIO") (class "Default")
      (node (ref "R28") (pin "1") (pinfunction "1_1") (pintype "passive"))
      (node (ref "U3") (pin "34") (pinfunction "JTMS/SWDIO_34") (pintype "passive"))
    )
    (net (code "34") (name "/Sensor_CLK") (class "Default")
      (node (ref "U3") (pin "39") (pinfunction "PB3/JTDO_39") (pintype "passive"))
      (node (ref "U6") (pin "23") (pinfunction "CLK_23") (pintype "passive"))
    )
    (net (code "35") (name "/Sensor_CLK_A") (class "Default")
      (node (ref "J1") (pin "14") (pintype "passive"))
      (node (ref "P3") (pin "4") (pintype "passive"))
    )
    (net (code "36") (name "/Sensor_CLK_B") (class "Default")
      (node (ref "J2") (pin "14") (pintype "passive"))
      (node (ref "P4") (pin "4") (pintype "passive"))
    )
    (net (code "37") (name "/Sensor_CS") (class "Default")
      (node (ref "U3") (pin "38") (pinfunction "PA15/JTDI_38") (pintype "passive"))
      (node (ref "U6") (pin "22") (pinfunction "nCS_22") (pintype "passive"))
    )
    (net (code "38") (name "/Sensor_CS_A") (class "Default")
      (node (ref "J1") (pin "16") (pintype "passive"))
      (node (ref "P3") (pin "5") (pintype "passive"))
    )
    (net (code "39") (name "/Sensor_CS_B") (class "Default")
      (node (ref "J2") (pin "16") (pintype "passive"))
      (node (ref "P4") (pin "5") (pintype "passive"))
    )
    (net (code "40") (name "/Sensor_MISO") (class "Default")
      (node (ref "U3") (pin "40") (pinfunction "PB4/JNTRST_40") (pintype "passive"))
      (node (ref "U6") (pin "9") (pinfunction "SDO/AD0_9") (pintype "passive"))
    )
    (net (code "41") (name "/Sensor_MISO_A") (class "Default")
      (node (ref "J1") (pin "12") (pintype "passive"))
      (node (ref "P3") (pin "3") (pintype "passive"))
    )
    (net (code "42") (name "/Sensor_MISO_B") (class "Default")
      (node (ref "J2") (pin "12") (pintype "passive"))
      (node (ref "P4") (pin "3") (pintype "passive"))
    )
    (net (code "43") (name "/Sensor_MOSI") (class "Default")
      (node (ref "U3") (pin "41") (pinfunction "PB5_41") (pintype "passive"))
      (node (ref "U6") (pin "24") (pinfunction "SDA/SDI_24") (pintype "passive"))
    )
    (net (code "44") (name "/Sensor_MOSI_A") (class "Default")
      (node (ref "J1") (pin "11") (pintype "passive"))
      (node (ref "P3") (pin "2") (pintype "passive"))
    )
    (net (code "45") (name "/Sensor_MOSI_B") (class "Default")
      (node (ref "J2") (pin "11") (pintype "passive"))
      (node (ref "P4") (pin "2") (pintype "passive"))
    )
    (net (code "46") (name "/USART1_RX") (class "Default")
      (node (ref "R32") (pin "1") (pinfunction "1_1") (pintype "passive"))
      (node (ref "U3") (pin "31") (pinfunction "PA10_31") (pintype "passive"))
    )
    (net (code "47") (name "/USART1_RX_A") (class "Default") (node (ref "J1") (pin "15") (pintype "passive")))
    (net (code "48") (name "/USART1_RX_B") (class "Default") (node (ref "J2") (pin "15") (pintype "passive")))
    (net (code "49") (name "/USART1_TX") (class "Default")
      (node (ref "R33") (pin "1") (pinfunction "1_1") (pintype "passive"))
      (node (ref "U3") (pin "30") (pinfunction "PA9_30") (pintype "passive"))
    )
    (net (code "50") (name "/USART1_TX_A") (class "Default") (node (ref "J1") (pin "17") (pintype "passive")))
    (net (code "51") (name "/USART1_TX_B") (class "Default") (node (ref "J2") (pin "17") (pintype "passive")))
    (net (code "52") (name "/USART3_RX") (class "Default")
      (node (ref "U3") (pin "22") (pinfunction "PB11_22") (pintype "passive"))
    )
    (net (code "53") (name "/USART3_TX") (class "Default")
      (node (ref "R30") (pin "2") (pinfunction "2_2") (pintype "passive"))
      (node (ref "U3") (pin "21") (pinfunction "PB10_21") (pintype "passive"))
    )
    (net (code "54") (name "/Voltage_ADC") (class "Default")
      (node (ref "C6") (pin "2") (pinfunction "2_2") (pintype "passive"))
      (node (ref "R1") (pin "2") (pinfunction "2_2") (pintype "passive"))
      (node (ref "R2") (pin "1") (pinfunction "1_1") (pintype "passive"))
      (node (ref "U3") (pin "10") (pinfunction "PA0_10") (pintype "passive"))
    )
    (net (code "55") (name "/WS2812A") (class "Default")
      (node (ref "R5") (pin "1") (pinfunction "1_1") (pintype "passive"))
      (node (ref "U3") (pin "42") (pinfunction "PB6_42") (pintype "passive"))
    )
    (net (code "56") (name "/WS2812B") (class "Default")
      (node (ref "R6") (pin "2") (pinfunction "2_2") (pintype "passive"))
      (node (ref "U3") (pin "45") (pinfunction "PB8_45") (pintype "passive"))
    )
    (net (code "57") (name "/YI") (class "Default")
      (node (ref "C21") (pin "1") (pinfunction "1_1") (pintype "passive"))
      (node (ref "U3") (pin "5") (pinfunction "OSCIN_5") (pintype "passive"))
      (node (ref "Y1") (pin "1") (pintype "passive"))
    )
    (net (code "58") (name "/YO") (class "Default")
      (node (ref "C24") (pin "1") (pinfunction "1_1") (pintype "passive"))
      (node (ref "U3") (pin "6") (pinfunction "OSCOUT_6") (pintype "passive"))
      (node (ref "Y1") (pin "3") (pintype "passive"))
    )
    (net (code "59") (name "BAT+") (class "Default")
      (node (ref "P6") (pin "1") (pintype "passive"))
      (node (ref "Q2") (pin "3") (pinfunction "S_3") (pintype "passive"))
      (node (ref "R49") (pin "2") (pinfunction "2_2") (pintype "passive"))
    )
    (net (code "60") (name "DC_3.3V") (class "Default")
      (node (ref "C26") (pin "1") (pinfunction "1_1") (pintype "passive"))
      (node (ref "C27") (pin "1") (pinfunction "1_1") (pintype "passive"))
      (node (ref "C9") (pin "2") (pinfunction "2_2") (pintype "passive"))
      (node (ref "L2") (pin "1") (pinfunction "1_1") (pintype "passive"))
      (node (ref "L3") (pin "1") (pinfunction "1_1") (pintype "passive"))
      (node (ref "R15") (pin "2") (pinfunction "2_2") (pintype "passive"))
      (node (ref "R16") (pin "2") (pinfunction "2_2") (pintype "passive"))
      (node (ref "R17") (pin "2") (pinfunction "2_2") (pintype "passive"))
      (node (ref "U1") (pin "5") (pinfunction "SHDN_5") (pintype "passive"))
      (node (ref "U4") (pin "5") (pinfunction "OUT_5") (pintype "passive"))
    )
    (net (code "61") (name "DGND") (class "Default")
      (node (ref "C1") (pin "2") (pinfunction "2_2") (pintype "passive"))
      (node (ref "C2") (pin "2") (pinfunction "2_2") (pintype "passive"))
      (node (ref "C20") (pin "2") (pinfunction "2_2") (pintype "passive"))
      (node (ref "C21") (pin "2") (pinfunction "2_2") (pintype "passive"))
      (node (ref "C22") (pin "2") (pinfunction "2_2") (pintype "passive"))
      (node (ref "C23") (pin "2") (pinfunction "2_2") (pintype "passive"))
      (node (ref "C24") (pin "2") (pinfunction "2_2") (pintype "passive"))
      (node (ref "C25") (pin "1") (pinfunction "1_1") (pintype "passive"))
      (node (ref "C26") (pin "2") (pinfunction "2_2") (pintype "passive"))
      (node (ref "C27") (pin "2") (pinfunction "2_2") (pintype "passive"))
      (node (ref "C3") (pin "2") (pinfunction "2_2") (pintype "passive"))
      (node (ref "C33") (pin "2") (pinfunction "2_2") (pintype "passive"))
      (node (ref "C34") (pin "1") (pinfunction "1_1") (pintype "passive"))
      (node (ref "C35") (pin "2") (pinfunction "2_2") (pintype "passive"))
      (node (ref "C36") (pin "1") (pinfunction "1_1") (pintype "passive"))
      (node (ref "C37") (pin "1") (pinfunction "1_1") (pintype "passive"))
      (node (ref "C38") (pin "1") (pinfunction "1_1") (pintype "passive"))
      (node (ref "C39") (pin "1") (pinfunction "1_1") (pintype "passive"))
      (node (ref "C4") (pin "2") (pinfunction "2_2") (pintype "passive"))
      (node (ref "C40") (pin "1") (pinfunction "1_1") (pintype "passive"))
      (node (ref "C41") (pin "1") (pinfunction "1_1") (pintype "passive"))
      (node (ref "C42") (pin "1") (pinfunction "1_1") (pintype "passive"))
      (node (ref "C43") (pin "1") (pinfunction "1_1") (pintype "passive"))
      (node (ref "C44") (pin "1") (pinfunction "1_1") (pintype "passive"))
      (node (ref "C45") (pin "1") (pinfunction "1_1") (pintype "passive"))
      (node (ref "C46") (pin "1") (pinfunction "1_1") (pintype "passive"))
      (node (ref "C47") (pin "2") (pinfunction "2_2") (pintype "passive"))
      (node (ref "C48") (pin "1") (pinfunction "1_1") (pintype "passive"))
      (node (ref "C5") (pin "1") (pinfunction "1_1") (pintype "passive"))
      (node (ref "C7") (pin "2") (pinfunction "2_2") (pintype "passive"))
      (node (ref "C9") (pin "1") (pinfunction "1_1") (pintype "passive"))
      (node (ref "J1") (pin "19") (pintype "passive"))
      (node (ref "J2") (pin "19") (pintype "passive"))
      (node (ref "K1") (pin "1") (pinfunction "1_1") (pintype "passive"))
      (node (ref "K1") (pin "2") (pinfunction "2_2") (pintype "passive"))
      (node (ref "LED1") (pin "1") (pinfunction "GND_1") (pintype "passive"))
      (node (ref "LED2") (pin "1") (pinfunction "GND_1") (pintype "passive"))
      (node (ref "LED3") (pin "1") (pinfunction "GND_1") (pintype "passive"))
      (node (ref "LED4") (pin "1") (pinfunction "GND_1") (pintype "passive"))
      (node (ref "LED5") (pin "1") (pinfunction "GND_1") (pintype "passive"))
      (node (ref "LED6") (pin "1") (pinfunction "GND_1") (pintype "passive"))
      (node (ref "P1") (pin "4") (pintype "passive"))
      (node (ref "P1") (pin "5") (pintype "passive"))
      (node (ref "P1") (pin "6") (pintype "passive"))
      (node (ref "P2") (pin "4") (pintype "passive"))
      (node (ref "P2") (pin "5") (pintype "passive"))
      (node (ref "P2") (pin "6") (pintype "passive"))
      (node (ref "P3") (pin "6") (pintype "passive"))
      (node (ref "P3") (pin "7") (pintype "passive"))
      (node (ref "P3") (pin "8") (pintype "passive"))
      (node (ref "P4") (pin "6") (pintype "passive"))
      (node (ref "P4") (pin "7") (pintype "passive"))
      (node (ref "P4") (pin "8") (pintype "passive"))
      (node (ref "P5") (pin "2") (pintype "passive"))
      (node (ref "R21") (pin "1") (pinfunction "1_1") (pintype "passive"))
      (node (ref "R26") (pin "1") (pinfunction "1_1") (pintype "passive"))
      (node (ref "R3") (pin "2") (pinfunction "2_2") (pintype "passive"))
      (node (ref "R4") (pin "1") (pinfunction "1_1") (pintype "passive"))
      (node (ref "R53") (pin "1") (pinfunction "1_1") (pintype "passive"))
      (node (ref "R9") (pin "2") (pinfunction "2_2") (pintype "passive"))
      (node (ref "U1") (pin "2") (pinfunction "GND_2") (pintype "passive"))
      (node (ref "U3") (pin "23") (pinfunction "VSS_1_23") (pintype "passive"))
      (node (ref "U3") (pin "35") (pinfunction "VSS_2_35") (pintype "passive"))
      (node (ref "U3") (pin "47") (pinfunction "VSS_3_47") (pintype "passive"))
      (node (ref "U3") (pin "8") (pinfunction "VSSA_8") (pintype "passive"))
      (node (ref "U4") (pin "2") (pinfunction "GND_2") (pintype "power_in"))
      (node (ref "U5") (pin "2") (pinfunction "GND_2") (pintype "power_in"))
      (node (ref "U6") (pin "18") (pinfunction "GND_18") (pintype "passive"))
      (node (ref "U6") (pin "20") (pinfunction "RESV_20") (pintype "passive"))
      (node (ref "Y1") (pin "2") (pinfunction "2_2") (pintype "passive"))
      (node (ref "Y1") (pin "4") (pinfunction "4_4") (pintype "passive"))
    )
    (net (code "62") (name "MPU_VCC") (class "Default")
      (node (ref "C33") (pin "1") (pinfunction "1_1") (pintype "passive"))
      (node (ref "C35") (pin "1") (pinfunction "1_1") (pintype "passive"))
      (node (ref "L3") (pin "2") (pinfunction "2_2") (pintype "passive"))
      (node (ref "R27") (pin "1") (pinfunction "1_1") (pintype "passive"))
      (node (ref "U6") (pin "13") (pinfunction "VDD_13") (pintype "passive"))
      (node (ref "U6") (pin "8") (pinfunction "VDDIO_8") (pintype "passive"))
    )
    (net (code "63") (name "Net-(B1--)") (class "Default")
      (node (ref "B1") (pin "2") (pinfunction "-_2") (pintype "passive"))
      (node (ref "D6") (pin "3") (pinfunction "S_3") (pintype "passive"))
      (node (ref "D7") (pin "1") (pinfunction "A_1") (pintype "passive"))
    )
    (net (code "64") (name "Net-(C19-Pad2)") (class "Default")
      (node (ref "C19") (pin "2") (pinfunction "2_2") (pintype "passive"))
      (node (ref "R12") (pin "2") (pinfunction "2_2") (pintype "passive"))
    )
    (net (code "65") (name "Net-(C43-Pad2)") (class "Default")
      (node (ref "C43") (pin "2") (pinfunction "2_2") (pintype "passive"))
      (node (ref "C44") (pin "2") (pinfunction "2_2") (pintype "passive"))
      (node (ref "L4") (pin "2") (pinfunction "2_2") (pintype "passive"))
      (node (ref "P5") (pin "1") (pintype "passive"))
    )
    (net (code "66") (name "Net-(D1-K)") (class "Default")
      (node (ref "C8") (pin "2") (pinfunction "2_2") (pintype "passive"))
      (node (ref "D1") (pin "2") (pinfunction "K_2") (pintype "passive"))
      (node (ref "L1") (pin "1") (pinfunction "1_1") (pintype "passive"))
      (node (ref "U2") (pin "9") (pinfunction "SW_9") (pintype "passive"))
    )
    (net (code "67") (name "Net-(D2-A)") (class "Default")
      (node (ref "D2") (pin "1") (pinfunction "A_1") (pintype "passive"))
      (node (ref "R15") (pin "1") (pinfunction "1_1") (pintype "passive"))
    )
    (net (code "68") (name "Net-(D3-A)") (class "Default")
      (node (ref "D3") (pin "1") (pinfunction "A_1") (pintype "passive"))
      (node (ref "R16") (pin "1") (pinfunction "1_1") (pintype "passive"))
    )
    (net (code "69") (name "Net-(D4-A)") (class "Default")
      (node (ref "D4") (pin "1") (pinfunction "A_1") (pintype "passive"))
      (node (ref "R17") (pin "1") (pinfunction "1_1") (pintype "passive"))
    )
    (net (code "70") (name "Net-(D5-G)") (class "Default")
      (node (ref "D5") (pin "1") (pinfunction "G_1") (pintype "passive"))
      (node (ref "R24") (pin "1") (pinfunction "1_1") (pintype "passive"))
      (node (ref "R25") (pin "2") (pinfunction "2_2") (pintype "passive"))
    )
    (net (code "71") (name "Net-(D5-S)") (class "Default")
      (node (ref "D5") (pin "3") (pinfunction "S_3") (pintype "passive"))
      (node (ref "R22") (pin "1") (pinfunction "1_1") (pintype "passive"))
      (node (ref "R23") (pin "1") (pinfunction "1_1") (pintype "passive"))
    )
    (net (code "72") (name "Net-(D6-G)") (class "Default")
      (node (ref "D6") (pin "1") (pinfunction "G_1") (pintype "passive"))
      (node (ref "R39") (pin "1") (pinfunction "1_1") (pintype "passive"))
      (node (ref "R40") (pin "1") (pinfunction "1_1") (pintype "passive"))
    )
    (net (code "73") (name "Net-(D9-A)") (class "Default")
      (node (ref "D9") (pin "1") (pinfunction "A_1") (pintype "passive"))
      (node (ref "R52") (pin "2") (pinfunction "2_2") (pintype "passive"))
    )
    (net (code "74") (name "Net-(D10-K)") (class "Default")
      (node (ref "D10") (pin "2") (pinfunction "K_2") (pintype "passive"))
      (node (ref "D8") (pin "2") (pinfunction "K_2") (pintype "passive"))
      (node (ref "K1") (pin "3") (pinfunction "3_3") (pintype "passive"))
      (node (ref "K1") (pin "4") (pinfunction "4_4") (pintype "passive"))
      (node (ref "R9") (pin "1") (pinfunction "1_1") (pintype "passive"))
    )
    (net (code "75") (name "Net-(LED1-DI)") (class "Default")
      (node (ref "LED1") (pin "2") (pinfunction "DI_2") (pintype "passive"))
      (node (ref "R5") (pin "2") (pinfunction "2_2") (pintype "passive"))
    )
    (net (code "76") (name "Net-(LED1-DO)") (class "Default")
      (node (ref "LED1") (pin "4") (pinfunction "DO_4") (pintype "passive"))
      (node (ref "LED3") (pin "2") (pinfunction "DI_2") (pintype "passive"))
    )
    (net (code "77") (name "Net-(LED2-DI)") (class "Default")
      (node (ref "LED2") (pin "2") (pinfunction "DI_2") (pintype "passive"))
      (node (ref "R6") (pin "1") (pinfunction "1_1") (pintype "passive"))
    )
    (net (code "78") (name "Net-(LED2-DO)") (class "Default")
      (node (ref "LED2") (pin "4") (pinfunction "DO_4") (pintype "passive"))
      (node (ref "LED4") (pin "2") (pinfunction "DI_2") (pintype "passive"))
    )
    (net (code "79") (name "Net-(LED3-DO)") (class "Default")
      (node (ref "LED3") (pin "4") (pinfunction "DO_4") (pintype "passive"))
      (node (ref "LED5") (pin "2") (pinfunction "DI_2") (pintype "passive"))
    )
    (net (code "80") (name "Net-(LED4-DO)") (class "Default")
      (node (ref "LED4") (pin "4") (pinfunction "DO_4") (pintype "passive"))
      (node (ref "LED6") (pin "2") (pinfunction "DI_2") (pintype "passive"))
    )
    (net (code "81") (name "Net-(P1-Pad1)") (class "Default")
      (node (ref "P1") (pin "1") (pintype "passive"))
      (node (ref "R37") (pin "1") (pinfunction "1_1") (pintype "passive"))
    )
    (net (code "82") (name "Net-(P1-Pad2)") (class "Default")
      (node (ref "P1") (pin "2") (pintype "passive"))
      (node (ref "R32") (pin "2") (pinfunction "2_2") (pintype "passive"))
    )
    (net (code "83") (name "Net-(P1-Pad3)") (class "Default")
      (node (ref "P1") (pin "3") (pintype "passive"))
      (node (ref "R33") (pin "2") (pinfunction "2_2") (pintype "passive"))
    )
    (net (code "84") (name "Net-(P2-Pad1)") (class "Default")
      (node (ref "P2") (pin "1") (pintype "passive"))
      (node (ref "R30") (pin "1") (pinfunction "1_1") (pintype "passive"))
    )
    (net (code "85") (name "Net-(P2-Pad2)") (class "Default")
      (node (ref "P2") (pin "2") (pintype "passive"))
      (node (ref "R28") (pin "2") (pinfunction "2_2") (pintype "passive"))
    )
    (net (code "86") (name "Net-(P2-Pad3)") (class "Default")
      (node (ref "P2") (pin "3") (pintype "passive"))
      (node (ref "R29") (pin "2") (pinfunction "2_2") (pintype "passive"))
    )
    (net (code "87") (name "Net-(Q2-G)") (class "Default")
      (node (ref "Q2") (pin "1") (pinfunction "G_1") (pintype "passive"))
      (node (ref "R48") (pin "2") (pinfunction "2_2") (pintype "passive"))
      (node (ref "R49") (pin "1") (pinfunction "1_1") (pintype "passive"))
    )
    (net (code "88") (name "Net-(Q3-B)") (class "Default")
      (node (ref "Q3") (pin "1") (pinfunction "B_1") (pintype "passive"))
      (node (ref "R50") (pin "2") (pinfunction "2_2") (pintype "passive"))
      (node (ref "R51") (pin "1") (pinfunction "1_1") (pintype "passive"))
    )
    (net (code "89") (name "Net-(U1-RS)") (class "Default")
      (node (ref "R3") (pin "1") (pinfunction "1_1") (pintype "passive"))
      (node (ref "U1") (pin "8") (pinfunction "RS_8") (pintype "passive"))
    )
    (net (code "90") (name "Net-(U2-BOOT)") (class "Default")
      (node (ref "C8") (pin "1") (pinfunction "1_1") (pintype "passive"))
      (node (ref "U2") (pin "1") (pinfunction "BOOT_1") (pintype "passive"))
    )
    (net (code "91") (name "Net-(U2-COMP)") (class "Default")
      (node (ref "C18") (pin "2") (pinfunction "2_2") (pintype "passive"))
      (node (ref "R12") (pin "1") (pinfunction "1_1") (pintype "passive"))
      (node (ref "U2") (pin "7") (pinfunction "COMP_7") (pintype "passive"))
    )
    (net (code "92") (name "Net-(U2-FB)") (class "Default")
      (node (ref "R13") (pin "2") (pinfunction "2_2") (pintype "passive"))
      (node (ref "R14") (pin "1") (pinfunction "1_1") (pintype "passive"))
      (node (ref "U2") (pin "6") (pinfunction "FB_6") (pintype "passive"))
    )
    (net (code "93") (name "Net-(U2-RT{slash}CLK)") (class "Default")
      (node (ref "R10") (pin "1") (pinfunction "1_1") (pintype "passive"))
      (node (ref "U2") (pin "5") (pinfunction "RT/CLK_5") (pintype "passive"))
    )
    (net (code "94") (name "Net-(U2-SS{slash}TR)") (class "Default")
      (node (ref "C14") (pin "2") (pinfunction "2_2") (pintype "passive"))
      (node (ref "U2") (pin "4") (pinfunction "SS/TR_4") (pintype "passive"))
    )
    (net (code "95") (name "Net-(U3-BOOT0)") (class "Default")
      (node (ref "R4") (pin "2") (pinfunction "2_2") (pintype "passive"))
      (node (ref "U3") (pin "44") (pinfunction "BOOT0_44") (pintype "passive"))
    )
    (net (code "96") (name "Net-(U4-NC)") (class "Default")
      (node (ref "C25") (pin "2") (pinfunction "2_2") (pintype "passive"))
      (node (ref "U4") (pin "4") (pinfunction "NC_4") (pintype "passive"))
    )
    (net (code "97") (name "Net-(U5-NR{slash}FB)") (class "Default")
      (node (ref "C40") (pin "2") (pinfunction "2_2") (pintype "passive"))
      (node (ref "U5") (pin "4") (pinfunction "NR/FB_4") (pintype "bidirectional"))
    )
    (net (code "98") (name "Net-(U5-OUT)") (class "Default")
      (node (ref "C41") (pin "2") (pinfunction "2_2") (pintype "passive"))
      (node (ref "C42") (pin "2") (pinfunction "2_2") (pintype "passive"))
      (node (ref "L4") (pin "1") (pinfunction "1_1") (pintype "passive"))
      (node (ref "U5") (pin "5") (pinfunction "OUT_5") (pintype "output"))
    )
    (net (code "99") (name "Net-(U6-FSYNC)") (class "Default")
      (node (ref "R26") (pin "2") (pinfunction "2_2") (pintype "passive"))
      (node (ref "U6") (pin "11") (pinfunction "FSYNC_11") (pintype "passive"))
    )
    (net (code "100") (name "Net-(U6-REGOUT)") (class "Default")
      (node (ref "C34") (pin "2") (pinfunction "2_2") (pintype "passive"))
      (node (ref "U6") (pin "10") (pinfunction "REGOUT_10") (pintype "passive"))
    )
    (net (code "101") (name "PGND") (class "Default")
      (node (ref "C10") (pin "1") (pinfunction "1_1") (pintype "passive"))
      (node (ref "C11") (pin "1") (pinfunction "1_1") (pintype "passive"))
      (node (ref "C12") (pin "1") (pinfunction "1_1") (pintype "passive"))
      (node (ref "C13") (pin "1") (pinfunction "1_1") (pintype "passive"))
      (node (ref "C14") (pin "1") (pinfunction "1_1") (pintype "passive"))
      (node (ref "C15") (pin "1") (pinfunction "1_1") (pintype "passive"))
      (node (ref "C16") (pin "1") (pinfunction "1_1") (pintype "passive"))
      (node (ref "C17") (pin "1") (pinfunction "1_1") (pintype "passive"))
      (node (ref "C18") (pin "1") (pinfunction "1_1") (pintype "passive"))
      (node (ref "C19") (pin "1") (pinfunction "1_1") (pintype "passive"))
      (node (ref "C6") (pin "1") (pinfunction "1_1") (pintype "passive"))
      (node (ref "D1") (pin "1") (pinfunction "A_1") (pintype "passive"))
      (node (ref "D5") (pin "2") (pinfunction "D_2") (pintype "passive"))
      (node (ref "D6") (pin "2") (pinfunction "D_2") (pintype "passive"))
      (node (ref "D9") (pin "2") (pinfunction "K_2") (pintype "passive"))
      (node (ref "J1") (pin "1") (pintype "passive"))
      (node (ref "J1") (pin "2") (pintype "passive"))
      (node (ref "J1") (pin "3") (pintype "passive"))
      (node (ref "J1") (pin "4") (pintype "passive"))
      (node (ref "J2") (pin "1") (pintype "passive"))
      (node (ref "J2") (pin "2") (pintype "passive"))
      (node (ref "J2") (pin "3") (pintype "passive"))
      (node (ref "J2") (pin "4") (pintype "passive"))
      (node (ref "P6") (pin "2") (pintype "passive"))
      (node (ref "Q3") (pin "2") (pinfunction "E_2") (pintype "passive"))
      (node (ref "R10") (pin "2") (pinfunction "2_2") (pintype "passive"))
      (node (ref "R13") (pin "1") (pinfunction "1_1") (pintype "passive"))
      (node (ref "R2") (pin "2") (pinfunction "2_2") (pintype "passive"))
      (node (ref "R21") (pin "2") (pinfunction "2_2") (pintype "passive"))
      (node (ref "R25") (pin "1") (pinfunction "1_1") (pintype "passive"))
      (node (ref "R40") (pin "2") (pinfunction "2_2") (pintype "passive"))
      (node (ref "R51") (pin "2") (pinfunction "2_2") (pintype "passive"))
      (node (ref "U2") (pin "0") (pinfunction "PAD_0") (pintype "passive"))
      (node (ref "U2") (pin "8") (pinfunction "GND_8") (pintype "passive"))
    )
    (net (code "102") (name "PVDD+") (class "Default")
      (node (ref "C10") (pin "2") (pinfunction "2_2") (pintype "passive"))
      (node (ref "C11") (pin "2") (pinfunction "2_2") (pintype "passive"))
      (node (ref "C12") (pin "2") (pinfunction "2_2") (pintype "passive"))
      (node (ref "C13") (pin "2") (pinfunction "2_2") (pintype "passive"))
      (node (ref "J1") (pin "5") (pintype "passive"))
      (node (ref "J1") (pin "6") (pintype "passive"))
      (node (ref "J1") (pin "7") (pintype "passive"))
      (node (ref "J1") (pin "8") (pintype "passive"))
      (node (ref "J2") (pin "5") (pintype "passive"))
      (node (ref "J2") (pin "6") (pintype "passive"))
      (node (ref "J2") (pin "7") (pintype "passive"))
      (node (ref "J2") (pin "8") (pintype "passive"))
      (node (ref "Q2") (pin "2") (pinfunction "D_2") (pintype "passive"))
      (node (ref "R1") (pin "1") (pinfunction "1_1") (pintype "passive"))
      (node (ref "U2") (pin "2") (pinfunction "VIN_2") (pintype "passive"))
    )
    (net (code "103") (name "VCC3.3V") (class "Default")
      (node (ref "C1") (pin "1") (pinfunction "1_1") (pintype "passive"))
      (node (ref "C2") (pin "1") (pinfunction "1_1") (pintype "passive"))
      (node (ref "C3") (pin "1") (pinfunction "1_1") (pintype "passive"))
      (node (ref "C4") (pin "1") (pinfunction "1_1") (pintype "passive"))
      (node (ref "C5") (pin "2") (pinfunction "2_2") (pintype "passive"))
      (node (ref "L2") (pin "2") (pinfunction "2_2") (pintype "passive"))
      (node (ref "R11") (pin "1") (pinfunction "1_1") (pintype "passive"))
      (node (ref "U3") (pin "1") (pinfunction "VBAT_1") (pintype "passive"))
      (node (ref "U3") (pin "24") (pinfunction "VDD_1_24") (pintype "passive"))
      (node (ref "U3") (pin "36") (pinfunction "VDD_2_36") (pintype "passive"))
      (node (ref "U3") (pin "48") (pinfunction "VDD_3_48") (pintype "passive"))
      (node (ref "U3") (pin "9") (pinfunction "VDDA_9") (pintype "passive"))
    )
    (net (code "104") (name "VCC3.3V1") (class "Default")
      (node (ref "J1") (pin "13") (pintype "passive"))
      (node (ref "P3") (pin "1") (pintype "passive"))
      (node (ref "R54") (pin "1") (pinfunction "1_1") (pintype "passive"))
    )
    (net (code "105") (name "VCC3.3V2") (class "Default")
      (node (ref "J2") (pin "13") (pintype "passive"))
      (node (ref "P4") (pin "1") (pintype "passive"))
    )
    (net (code "106") (name "VCC_5.0V") (class "Default")
      (node (ref "B1") (pin "1") (pinfunction "+_1") (pintype "passive"))
      (node (ref "C15") (pin "2") (pinfunction "2_2") (pintype "passive"))
      (node (ref "C16") (pin "2") (pinfunction "2_2") (pintype "passive"))
      (node (ref "C17") (pin "2") (pinfunction "2_2") (pintype "passive"))
      (node (ref "C22") (pin "1") (pinfunction "1_1") (pintype "passive"))
      (node (ref "C23") (pin "1") (pinfunction "1_1") (pintype "passive"))
      (node (ref "C36") (pin "2") (pinfunction "2_2") (pintype "passive"))
      (node (ref "C37") (pin "2") (pinfunction "2_2") (pintype "passive"))
      (node (ref "C38") (pin "2") (pinfunction "2_2") (pintype "passive"))
      (node (ref "C39") (pin "2") (pinfunction "2_2") (pintype "passive"))
      (node (ref "C45") (pin "2") (pinfunction "2_2") (pintype "passive"))
      (node (ref "C46") (pin "2") (pinfunction "2_2") (pintype "passive"))
      (node (ref "C47") (pin "1") (pinfunction "1_1") (pintype "passive"))
      (node (ref "C48") (pin "2") (pinfunction "2_2") (pintype "passive"))
      (node (ref "C7") (pin "1") (pinfunction "1_1") (pintype "passive"))
      (node (ref "D7") (pin "2") (pinfunction "K_2") (pintype "passive"))
      (node (ref "L1") (pin "2") (pinfunction "2_2") (pintype "passive"))
      (node (ref "LED1") (pin "3") (pinfunction "VCC_3") (pintype "passive"))
      (node (ref "LED2") (pin "3") (pinfunction "VCC_3") (pintype "passive"))
      (node (ref "LED3") (pin "3") (pinfunction "VCC_3") (pintype "passive"))
      (node (ref "LED4") (pin "3") (pinfunction "VCC_3") (pintype "passive"))
      (node (ref "LED5") (pin "3") (pinfunction "VCC_3") (pintype "passive"))
      (node (ref "LED6") (pin "3") (pinfunction "VCC_3") (pintype "passive"))
      (node (ref "R14") (pin "2") (pinfunction "2_2") (pintype "passive"))
      (node (ref "R22") (pin "2") (pinfunction "2_2") (pintype "passive"))
      (node (ref "R23") (pin "2") (pinfunction "2_2") (pintype "passive"))
      (node (ref "R37") (pin "2") (pinfunction "2_2") (pintype "passive"))
      (node (ref "R52") (pin "1") (pinfunction "1_1") (pintype "passive"))
      (node (ref "U1") (pin "3") (pinfunction "VCC_3") (pintype "passive"))
      (node (ref "U4") (pin "1") (pinfunction "IN_1") (pintype "passive"))
      (node (ref "U4") (pin "3") (pinfunction "CE_3") (pintype "passive"))
      (node (ref "U5") (pin "1") (pinfunction "IN_1") (pintype "input"))
      (node (ref "U5") (pin "3") (pinfunction "EN_3") (pintype "passive"))
    )
    (net (code "107") (name "unconnected-(J3-Pad10)") (class "Default")
      (node (ref "J3") (pin "10") (pintype "passive"))
    )
    (net (code "108") (name "unconnected-(J3-Pad12)") (class "Default")
      (node (ref "J3") (pin "12") (pintype "passive"))
    )
    (net (code "109") (name "unconnected-(J4-Pad10)") (class "Default")
      (node (ref "J4") (pin "10") (pintype "passive"))
    )
    (net (code "110") (name "unconnected-(J4-Pad12)") (class "Default")
      (node (ref "J4") (pin "12") (pintype "passive"))
    )
    (net (code "111") (name "unconnected-(LED5-DO-Pad4)") (class "Default")
      (node (ref "LED5") (pin "4") (pinfunction "DO_4") (pintype "passive"))
    )
    (net (code "112") (name "unconnected-(LED6-DO-Pad4)") (class "Default")
      (node (ref "LED6") (pin "4") (pinfunction "DO_4") (pintype "passive"))
    )
    (net (code "113") (name "unconnected-(P5-Pad9)") (class "Default")
      (node (ref "P5") (pin "9") (pintype "passive"))
    )
    (net (code "114") (name "unconnected-(P5-Pad10)") (class "Default")
      (node (ref "P5") (pin "10") (pintype "passive"))
    )
    (net (code "115") (name "unconnected-(P6-Pad3)") (class "Default")
      (node (ref "P6") (pin "3") (pintype "passive"))
    )
    (net (code "116") (name "unconnected-(P6-Pad4)") (class "Default")
      (node (ref "P6") (pin "4") (pintype "passive"))
    )
    (net (code "117") (name "unconnected-(P6-Pad5)") (class "Default")
      (node (ref "P6") (pin "5") (pintype "passive"))
    )
    (net (code "118") (name "unconnected-(P9-Pad4)") (class "Default")
      (node (ref "P9") (pin "4") (pintype "passive"))
    )
    (net (code "119") (name "unconnected-(P9-Pad5)") (class "Default")
      (node (ref "P9") (pin "5") (pintype "passive"))
    )
    (net (code "120") (name "unconnected-(P10-Pad4)") (class "Default")
      (node (ref "P10") (pin "4") (pintype "passive"))
    )
    (net (code "121") (name "unconnected-(P10-Pad5)") (class "Default")
      (node (ref "P10") (pin "5") (pintype "passive"))
    )
    (net (code "122") (name "unconnected-(U2-EN-Pad3)") (class "Default")
      (node (ref "U2") (pin "3") (pinfunction "EN_3") (pintype "passive"))
    )
    (net (code "123") (name "unconnected-(U2-PWRGD-Pad10)") (class "Default")
      (node (ref "U2") (pin "10") (pinfunction "PWRGD_10") (pintype "passive"))
    )
    (net (code "124") (name "unconnected-(U3-PA1-Pad11)") (class "Default")
      (node (ref "U3") (pin "11") (pinfunction "PA1_11") (pintype "passive"))
    )
    (net (code "125") (name "unconnected-(U3-PA2-Pad12)") (class "Default")
      (node (ref "U3") (pin "12") (pinfunction "PA2_12") (pintype "passive"))
    )
    (net (code "126") (name "unconnected-(U3-PB1-Pad19)") (class "Default")
      (node (ref "U3") (pin "19") (pinfunction "PB1_19") (pintype "passive"))
    )
    (net (code "127") (name "unconnected-(U3-PB9-Pad46)") (class "Default")
      (node (ref "U3") (pin "46") (pinfunction "PB9_46") (pintype "passive"))
    )
    (net (code "128") (name "unconnected-(U3-PB15-Pad28)") (class "Default")
      (node (ref "U3") (pin "28") (pinfunction "PB15_28") (pintype "passive"))
    )
    (net (code "129") (name "unconnected-(U6-AUX_CL-Pad7)") (class "Default")
      (node (ref "U6") (pin "7") (pinfunction "AUX_CL_7") (pintype "passive"))
    )
    (net (code "130") (name "unconnected-(U6-AUX_DA-Pad21)") (class "Default")
      (node (ref "U6") (pin "21") (pinfunction "AUX_DA_21") (pintype "passive"))
    )
    (net (code "131") (name "unconnected-(U6-NC-Pad1)") (class "Default")
      (node (ref "U6") (pin "1") (pinfunction "NC_1") (pintype "passive"))
    )
    (net (code "132") (name "unconnected-(U6-NC-Pad2)") (class "Default")
      (node (ref "U6") (pin "2") (pinfunction "NC_2") (pintype "passive"))
    )
    (net (code "133") (name "unconnected-(U6-NC-Pad3)") (class "Default")
      (node (ref "U6") (pin "3") (pinfunction "NC_3") (pintype "passive"))
    )
    (net (code "134") (name "unconnected-(U6-NC-Pad4)") (class "Default")
      (node (ref "U6") (pin "4") (pinfunction "NC_4") (pintype "passive"))
    )
    (net (code "135") (name "unconnected-(U6-NC-Pad5)") (class "Default")
      (node (ref "U6") (pin "5") (pinfunction "NC_5") (pintype "passive"))
    )
    (net (code "136") (name "unconnected-(U6-NC-Pad6)") (class "Default")
      (node (ref "U6") (pin "6") (pinfunction "NC_6") (pintype "passive"))
    )
    (net (code "137") (name "unconnected-(U6-NC-Pad14)") (class "Default")
      (node (ref "U6") (pin "14") (pinfunction "NC_14") (pintype "passive"))
    )
    (net (code "138") (name "unconnected-(U6-NC-Pad15)") (class "Default")
      (node (ref "U6") (pin "15") (pinfunction "NC_15") (pintype "passive"))
    )
    (net (code "139") (name "unconnected-(U6-NC-Pad16)") (class "Default")
      (node (ref "U6") (pin "16") (pinfunction "NC_16") (pintype "passive"))
    )
    (net (code "140") (name "unconnected-(U6-NC-Pad17)") (class "Default")
      (node (ref "U6") (pin "17") (pinfunction "NC_17") (pintype "passive"))
    )
    (net (code "141") (name "unconnected-(U6-RESV-Pad19)") (class "Default")
      (node (ref "U6") (pin "19") (pinfunction "RESV_19") (pintype "passive"))
    )
  )
)
